# Sheet1.net
KiCad netlist of a schematic drawn in Altium Designer
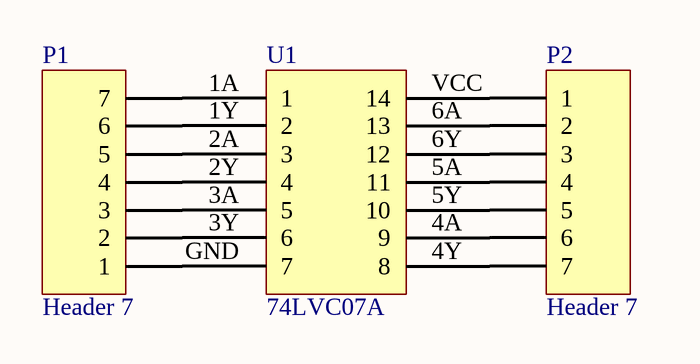
[diagram p0: Sheet1.SchDoc]

(export (version "E")
  (design (tool "Eeschema 10.0.6"))
  (components
    (comp (ref "P1")
      (value "Header 7")
      (footprint "HDR1X7")
      (description "Header, 7-Pin")
      (fields (field (name "PUBLISHER") "Altium Limited"))
      (libsource (lib "Miscellaneous Connectors") (part "Header 7"))
    )
    (comp (ref "P2")
      (value "Header 7")
      (footprint "HDR1X7")
      (description "Header, 7-Pin")
      (fields (field (name "PUBLISHER") "Altium Limited"))
      (libsource (lib "") (part "Header 7_1"))
    )
    (comp (ref "U1")
      (value "Component_1")
      (footprint "PCBComponent_1")
      (libsource (lib "74LVC07A") (part "Component_1"))
    )
  )
  (nets
    (net (code "1") (name "Net-(U1-1)") (class "Default")
      (node (ref "P1") (pin "7") (pinfunction "7_7") (pintype "passive"))
      (node (ref "U1") (pin "1A") (pinfunction "1_1A") (pintype "passive"))
    )
    (net (code "2") (name "Net-(U1-2)") (class "Default")
      (node (ref "P1") (pin "6") (pinfunction "6_6") (pintype "passive"))
      (node (ref "U1") (pin "1Y") (pinfunction "2_1Y") (pintype "passive"))
    )
    (net (code "3") (name "Net-(U1-3)") (class "Default")
      (node (ref "P1") (pin "5") (pinfunction "5_5") (pintype "passive"))
      (node (ref "U1") (pin "2A") (pinfunction "3_2A") (pintype "passive"))
    )
    (net (code "4") (name "Net-(U1-4)") (class "Default")
      (node (ref "P1") (pin "4") (pinfunction "4_4") (pintype "passive"))
      (node (ref "U1") (pin "2Y") (pinfunction "4_2Y") (pintype "passive"))
    )
    (net (code "5") (name "Net-(U1-5)") (class "Default")
      (node (ref "P1") (pin "3") (pinfunction "3_3") (pintype "passive"))
      (node (ref "U1") (pin "3A") (pinfunction "5_3A") (pintype "passive"))
    )
    (net (code "6") (name "Net-(U1-6)") (class "Default")
      (node (ref "P1") (pin "2") (pinfunction "2_2") (pintype "passive"))
      (node (ref "U1") (pin "3Y") (pinfunction "6_3Y") (pintype "passive"))
    )
    (net (code "7") (name "Net-(U1-7)") (class "Default")
      (node (ref "P1") (pin "1") (pinfunction "1_1") (pintype "passive"))
      (node (ref "U1") (pin "GND") (pinfunction "7_GND") (pintype "passive"))
    )
    (net (code "8") (name "Net-(U1-8)") (class "Default")
      (node (ref "P2") (pin "7") (pinfunction "7_7") (pintype "passive"))
      (node (ref "U1") (pin "4Y") (pinfunction "8_4Y") (pintype "passive"))
    )
    (net (code "9") (name "Net-(U1-9)") (class "Default")
      (node (ref "P2") (pin "6") (pinfunction "6_6") (pintype "passive"))
      (node (ref "U1") (pin "4A") (pinfunction "9_4A") (pintype "passive"))
    )
    (net (code "10") (name "Net-(U1-10)") (class "Default")
      (node (ref "P2") (pin "5") (pinfunction "5_5") (pintype "passive"))
      (node (ref "U1") (pin "5Y") (pinfunction "10_5Y") (pintype "passive"))
    )
    (net (code "11") (name "Net-(U1-11)") (class "Default")
      (node (ref "P2") (pin "4") (pinfunction "4_4") (pintype "passive"))
      (node (ref "U1") (pin "5A") (pinfunction "11_5A") (pintype "passive"))
    )
    (net (code "12") (name "Net-(U1-12)") (class "Default")
      (node (ref "P2") (pin "3") (pinfunction "3_3") (pintype "passive"))
      (node (ref "U1") (pin "6Y") (pinfunction "12_6Y") (pintype "passive"))
    )
    (net (code "13") (name "Net-(U1-13)") (class "Default")
      (node (ref "P2") (pin "2") (pinfunction "2_2") (pintype "passive"))
      (node (ref "U1") (pin "6A") (pinfunction "13_6A") (pintype "passive"))
    )
    (net (code "14") (name "Net-(U1-14)") (class "Default")
      (node (ref "P2") (pin "1") (pinfunction "1_1") (pintype "passive"))
      (node (ref "U1") (pin "VCC") (pinfunction "14_VCC") (pintype "passive"))
    )
  )
)
